# SCH_EasyEDA.net
KiCad netlist of a schematic drawn in EasyEDA
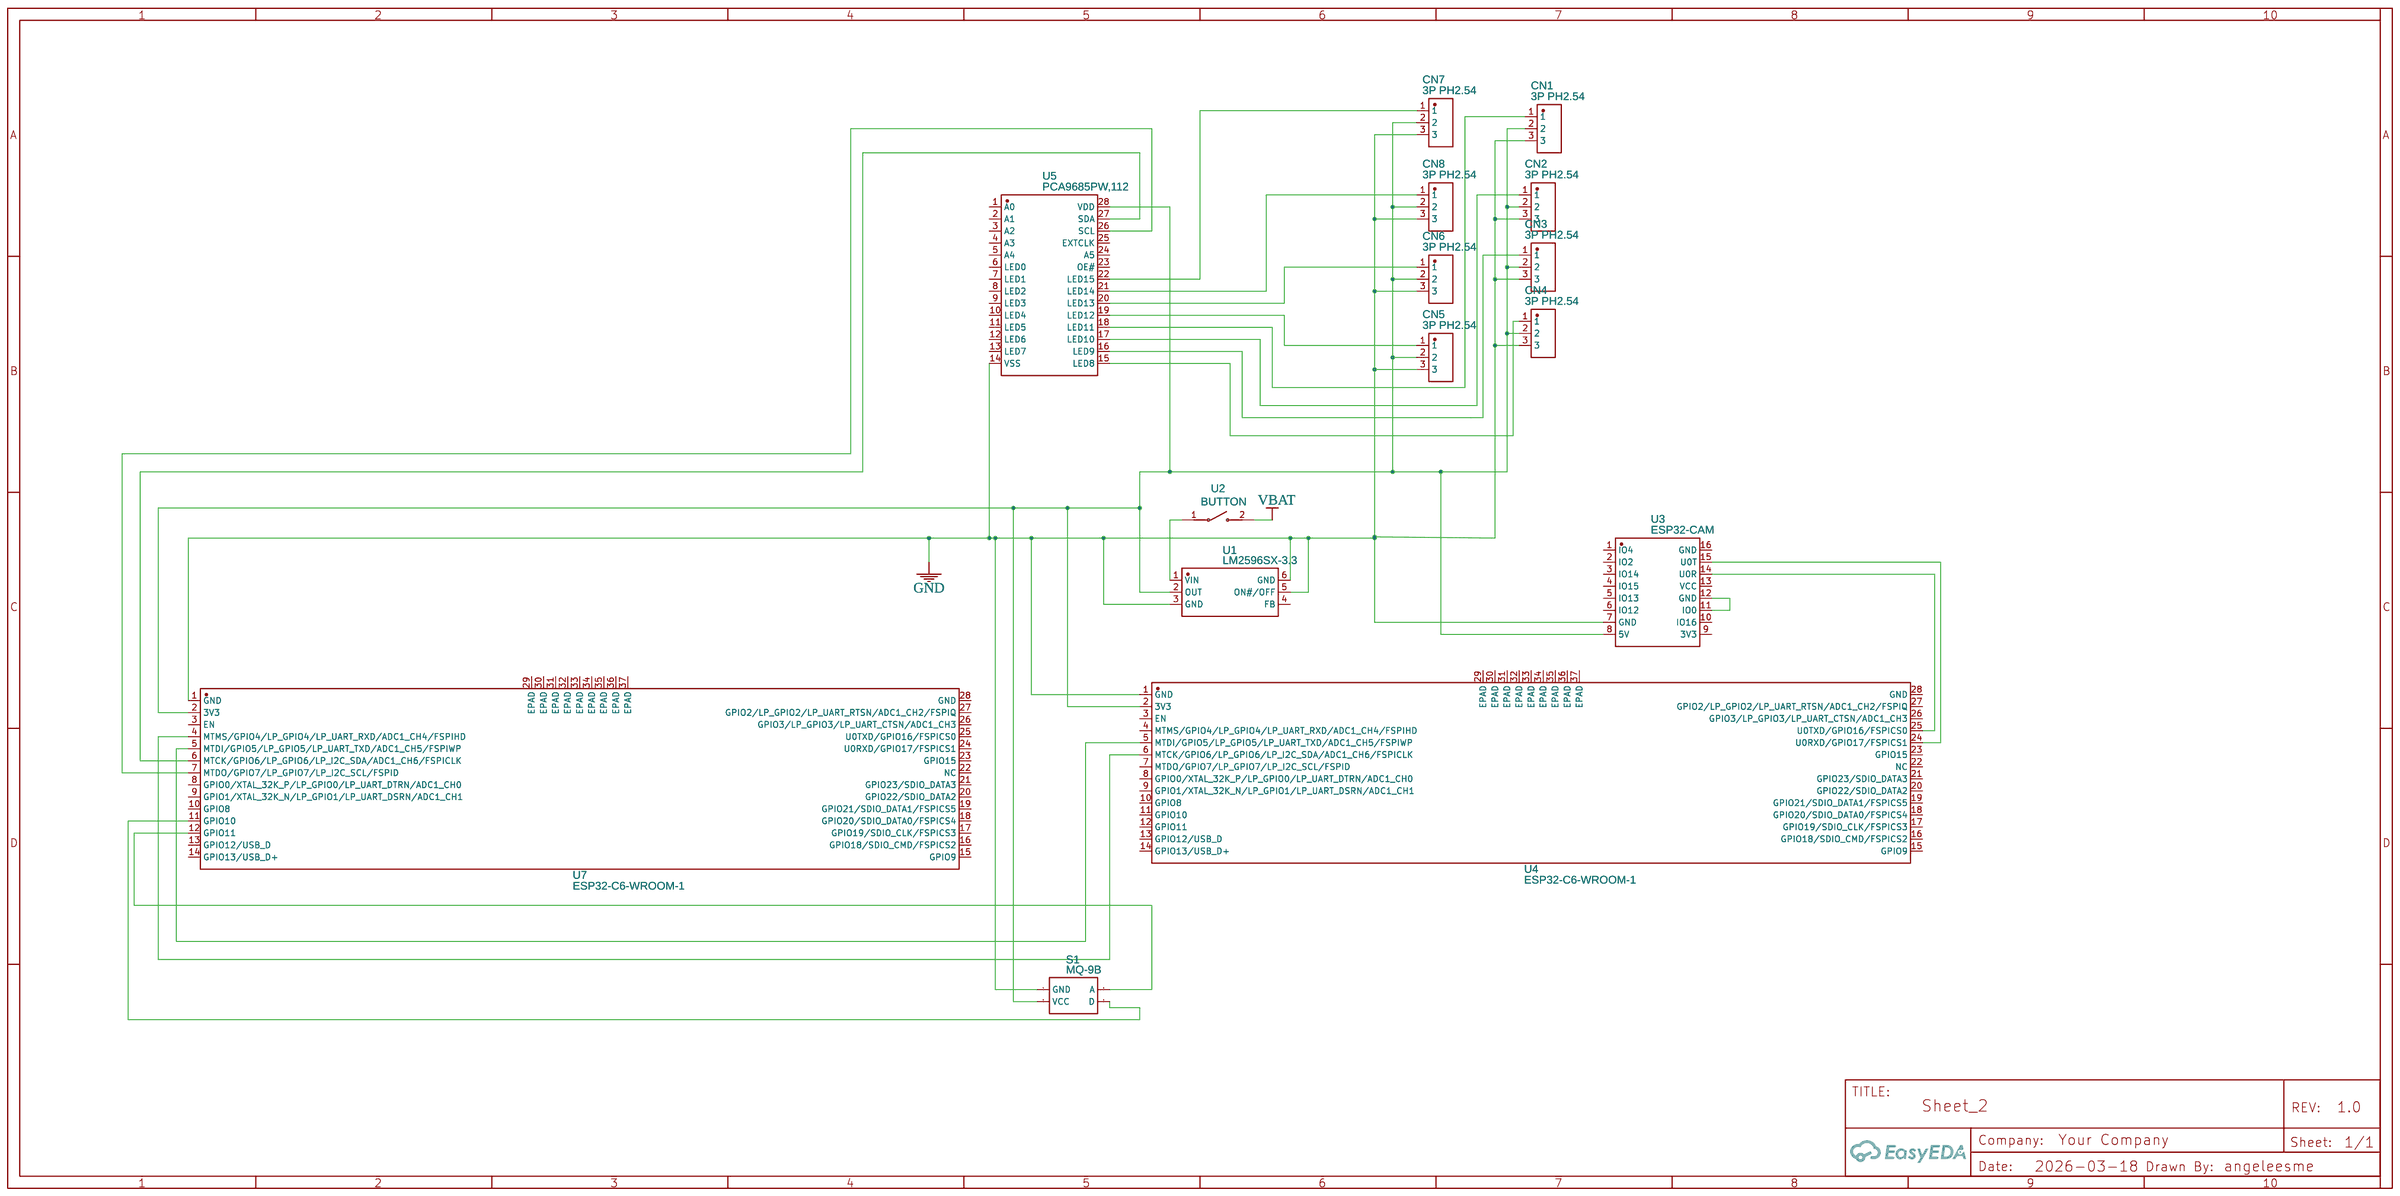
[diagram p0: schematic sheet]

(export (version "E")
  (design (tool "Eeschema 10.0.6"))
  (components
    (comp (ref "CN1") (value "3P PH2.54") (libsource (lib "") (part "3P PH2.54")))
    (comp (ref "CN2") (value "3P PH2.54") (libsource (lib "") (part "3P PH2.54")))
    (comp (ref "CN3") (value "3P PH2.54") (libsource (lib "") (part "3P PH2.54")))
    (comp (ref "CN4") (value "3P PH2.54") (libsource (lib "") (part "3P PH2.54")))
    (comp (ref "CN5") (value "3P PH2.54") (libsource (lib "") (part "3P PH2.54")))
    (comp (ref "CN6") (value "3P PH2.54") (libsource (lib "") (part "3P PH2.54")))
    (comp (ref "CN7") (value "3P PH2.54") (libsource (lib "") (part "3P PH2.54")))
    (comp (ref "CN8") (value "3P PH2.54") (libsource (lib "") (part "3P PH2.54")))
    (comp (ref "S1") (value "MQ-9B") (libsource (lib "") (part "HDR-F-2.54_2x2")))
    (comp (ref "U1")
      (value "LM2596SX-3.3")
      (fields (field (name "Manufacturer") "Slkor(萨科微)"))
      (libsource (lib "") (part "LM2596SX-3.3"))
    )
    (comp (ref "U2") (value "BUTTON") (libsource (lib "") (part "BUTTON")))
    (comp (ref "U3")
      (value "ESP32-CAM")
      (fields (field (name "Manufacturer") "Ai-Thinker(安信可)"))
      (libsource (lib "") (part "ESP32-CAM"))
    )
    (comp (ref "U4") (value "ESP32-C6-WROOM-1") (libsource (lib "") (part "ESP32-C6-WROOM-1")))
    (comp (ref "U5")
      (value "PCA9685PW,112")
      (fields (field (name "Manufacturer") "NXP(恩智浦)"))
      (libsource (lib "") (part "PCA9685PW,112"))
    )
    (comp (ref "U7") (value "ESP32-C6-WROOM-1") (libsource (lib "") (part "ESP32-C6-WROOM-1")))
  )
  (nets
    (net (code "1") (name "GND") (class "Default")
      (node (ref "CN1") (pin "3") (pinfunction "3_3") (pintype "unspecified"))
      (node (ref "CN2") (pin "3") (pinfunction "3_3") (pintype "unspecified"))
      (node (ref "CN3") (pin "3") (pinfunction "3_3") (pintype "unspecified"))
      (node (ref "CN4") (pin "3") (pinfunction "3_3") (pintype "unspecified"))
      (node (ref "CN5") (pin "3") (pinfunction "3_3") (pintype "unspecified"))
      (node (ref "CN6") (pin "3") (pinfunction "3_3") (pintype "unspecified"))
      (node (ref "CN7") (pin "3") (pinfunction "3_3") (pintype "unspecified"))
      (node (ref "CN8") (pin "3") (pinfunction "3_3") (pintype "unspecified"))
      (node (ref "S1") (pin "1") (pinfunction "GND_1") (pintype "unspecified"))
      (node (ref "U1") (pin "3") (pinfunction "GND_3") (pintype "unspecified"))
      (node (ref "U1") (pin "5") (pinfunction "ON#/OFF_5") (pintype "unspecified"))
      (node (ref "U1") (pin "6") (pinfunction "GND_6") (pintype "unspecified"))
      (node (ref "U3") (pin "7") (pinfunction "GND_7") (pintype "unspecified"))
      (node (ref "U4") (pin "1") (pinfunction "GND_1") (pintype "unspecified"))
      (node (ref "U5") (pin "14") (pinfunction "VSS_14") (pintype "unspecified"))
      (node (ref "U7") (pin "1") (pinfunction "GND_1") (pintype "unspecified"))
    )
    (net (code "2") (name "Net-(S1-A)") (class "Default")
      (node (ref "S1") (pin "2") (pinfunction "A_2") (pintype "unspecified"))
      (node (ref "U7") (pin "12") (pinfunction "GPIO11_12") (pintype "unspecified"))
    )
    (net (code "3") (name "Net-(S1-D)") (class "Default")
      (node (ref "S1") (pin "4") (pinfunction "D_4") (pintype "unspecified"))
      (node (ref "U7") (pin "11") (pinfunction "GPIO10_11") (pintype "unspecified"))
    )
    (net (code "4") (name "Net-(S1-VCC)") (class "Default")
      (node (ref "CN1") (pin "2") (pinfunction "2_2") (pintype "unspecified"))
      (node (ref "CN2") (pin "2") (pinfunction "2_2") (pintype "unspecified"))
      (node (ref "CN3") (pin "2") (pinfunction "2_2") (pintype "unspecified"))
      (node (ref "CN4") (pin "2") (pinfunction "2_2") (pintype "unspecified"))
      (node (ref "CN5") (pin "2") (pinfunction "2_2") (pintype "unspecified"))
      (node (ref "CN6") (pin "2") (pinfunction "2_2") (pintype "unspecified"))
      (node (ref "CN7") (pin "2") (pinfunction "2_2") (pintype "unspecified"))
      (node (ref "CN8") (pin "2") (pinfunction "2_2") (pintype "unspecified"))
      (node (ref "S1") (pin "3") (pinfunction "VCC_3") (pintype "unspecified"))
      (node (ref "U1") (pin "2") (pinfunction "OUT_2") (pintype "unspecified"))
      (node (ref "U3") (pin "8") (pinfunction "5V_8") (pintype "unspecified"))
      (node (ref "U4") (pin "2") (pinfunction "3V3_2") (pintype "unspecified"))
      (node (ref "U5") (pin "28") (pinfunction "VDD_28") (pintype "unspecified"))
      (node (ref "U7") (pin "2") (pinfunction "3V3_2") (pintype "unspecified"))
    )
    (net (code "5") (name "Net-(U1-VIN)") (class "Default")
      (node (ref "U1") (pin "1") (pinfunction "VIN_1") (pintype "unspecified"))
      (node (ref "U2") (pin "1") (pinfunction "1_1") (pintype "unspecified"))
    )
    (net (code "6") (name "Net-(U3-IO0)") (class "Default")
      (node (ref "U3") (pin "11") (pinfunction "IO0_11") (pintype "unspecified"))
      (node (ref "U3") (pin "12") (pinfunction "GND_12") (pintype "unspecified"))
    )
    (net (code "7") (name "Net-(U3-U0R)") (class "Default")
      (node (ref "U3") (pin "14") (pinfunction "U0R_14") (pintype "unspecified"))
      (node (ref "U4") (pin "25") (pinfunction "U0TXD/GPIO16/FSPICS0_25") (pintype "unspecified"))
    )
    (net (code "8") (name "Net-(U3-U0T)") (class "Default")
      (node (ref "U3") (pin "15") (pinfunction "U0T_15") (pintype "unspecified"))
      (node (ref "U4") (pin "24") (pinfunction "U0RXD/GPIO17/FSPICS1_24") (pintype "unspecified"))
    )
    (net (code "9") (name "Net-(U4-MTCK{slash}GPIO6{slash}LP_GPIO6{slash}LP_I2C_SDA{slash}ADC1_CH6{slash}FSPICLK)") (class "Default")
      (node (ref "U4") (pin "6") (pinfunction "MTCK/GPIO6/LP_GPIO6/LP_I2C_SDA/ADC1_CH6/FSPICLK_6") (pintype "unspecified"))
      (node (ref "U7") (pin "4") (pinfunction "MTMS/GPIO4/LP_GPIO4/LP_UART_RXD/ADC1_CH4/FSPIHD_4") (pintype "unspecified"))
    )
    (net (code "10") (name "Net-(U4-MTDI{slash}GPIO5{slash}LP_GPIO5{slash}LP_UART_TXD{slash}ADC1_CH5{slash}FSPIWP)") (class "Default")
      (node (ref "U4") (pin "5") (pinfunction "MTDI/GPIO5/LP_GPIO5/LP_UART_TXD/ADC1_CH5/FSPIWP_5") (pintype "unspecified"))
      (node (ref "U7") (pin "5") (pinfunction "MTDI/GPIO5/LP_GPIO5/LP_UART_TXD/ADC1_CH5/FSPIWP_5") (pintype "unspecified"))
    )
    (net (code "11") (name "Net-(U5-LED8)") (class "Default")
      (node (ref "CN4") (pin "1") (pinfunction "1_1") (pintype "unspecified"))
      (node (ref "U5") (pin "15") (pinfunction "LED8_15") (pintype "unspecified"))
    )
    (net (code "12") (name "Net-(U5-LED9)") (class "Default")
      (node (ref "CN3") (pin "1") (pinfunction "1_1") (pintype "unspecified"))
      (node (ref "U5") (pin "16") (pinfunction "LED9_16") (pintype "unspecified"))
    )
    (net (code "13") (name "Net-(U5-LED10)") (class "Default")
      (node (ref "CN2") (pin "1") (pinfunction "1_1") (pintype "unspecified"))
      (node (ref "U5") (pin "17") (pinfunction "LED10_17") (pintype "unspecified"))
    )
    (net (code "14") (name "Net-(U5-LED11)") (class "Default")
      (node (ref "CN1") (pin "1") (pinfunction "1_1") (pintype "unspecified"))
      (node (ref "U5") (pin "18") (pinfunction "LED11_18") (pintype "unspecified"))
    )
    (net (code "15") (name "Net-(U5-LED12)") (class "Default")
      (node (ref "CN5") (pin "1") (pinfunction "1_1") (pintype "unspecified"))
      (node (ref "U5") (pin "19") (pinfunction "LED12_19") (pintype "unspecified"))
    )
    (net (code "16") (name "Net-(U5-LED13)") (class "Default")
      (node (ref "CN6") (pin "1") (pinfunction "1_1") (pintype "unspecified"))
      (node (ref "U5") (pin "20") (pinfunction "LED13_20") (pintype "unspecified"))
    )
    (net (code "17") (name "Net-(U5-LED14)") (class "Default")
      (node (ref "CN8") (pin "1") (pinfunction "1_1") (pintype "unspecified"))
      (node (ref "U5") (pin "21") (pinfunction "LED14_21") (pintype "unspecified"))
    )
    (net (code "18") (name "Net-(U5-LED15)") (class "Default")
      (node (ref "CN7") (pin "1") (pinfunction "1_1") (pintype "unspecified"))
      (node (ref "U5") (pin "22") (pinfunction "LED15_22") (pintype "unspecified"))
    )
    (net (code "19") (name "Net-(U5-SCL)") (class "Default")
      (node (ref "U5") (pin "26") (pinfunction "SCL_26") (pintype "unspecified"))
      (node (ref "U7") (pin "7") (pinfunction "MTDO/GPIO7/LP_GPIO7/LP_I2C_SCL/FSPID_7") (pintype "unspecified"))
    )
    (net (code "20") (name "Net-(U5-SDA)") (class "Default")
      (node (ref "U5") (pin "27") (pinfunction "SDA_27") (pintype "unspecified"))
      (node (ref "U7") (pin "6") (pinfunction "MTCK/GPIO6/LP_GPIO6/LP_I2C_SDA/ADC1_CH6/FSPICLK_6") (pintype "unspecified"))
    )
    (net (code "21") (name "VBAT") (class "Default")
      (node (ref "U2") (pin "2") (pinfunction "2_2") (pintype "unspecified"))
    )
    (net (code "22") (name "unconnected-(U1-FB-Pad4)") (class "Default")
      (node (ref "U1") (pin "4") (pinfunction "FB_4") (pintype "unspecified"))
    )
    (net (code "23") (name "unconnected-(U3-3V3-Pad9)") (class "Default")
      (node (ref "U3") (pin "9") (pinfunction "3V3_9") (pintype "unspecified"))
    )
    (net (code "24") (name "unconnected-(U3-GND-Pad16)") (class "Default")
      (node (ref "U3") (pin "16") (pinfunction "GND_16") (pintype "unspecified"))
    )
    (net (code "25") (name "unconnected-(U3-IO2-Pad2)") (class "Default")
      (node (ref "U3") (pin "2") (pinfunction "IO2_2") (pintype "unspecified"))
    )
    (net (code "26") (name "unconnected-(U3-IO4-Pad1)") (class "Default")
      (node (ref "U3") (pin "1") (pinfunction "IO4_1") (pintype "unspecified"))
    )
    (net (code "27") (name "unconnected-(U3-IO12-Pad6)") (class "Default")
      (node (ref "U3") (pin "6") (pinfunction "IO12_6") (pintype "unspecified"))
    )
    (net (code "28") (name "unconnected-(U3-IO13-Pad5)") (class "Default")
      (node (ref "U3") (pin "5") (pinfunction "IO13_5") (pintype "unspecified"))
    )
    (net (code "29") (name "unconnected-(U3-IO14-Pad3)") (class "Default")
      (node (ref "U3") (pin "3") (pinfunction "IO14_3") (pintype "unspecified"))
    )
    (net (code "30") (name "unconnected-(U3-IO15-Pad4)") (class "Default")
      (node (ref "U3") (pin "4") (pinfunction "IO15_4") (pintype "unspecified"))
    )
    (net (code "31") (name "unconnected-(U3-IO16-Pad10)") (class "Default")
      (node (ref "U3") (pin "10") (pinfunction "IO16_10") (pintype "unspecified"))
    )
    (net (code "32") (name "unconnected-(U3-VCC-Pad13)") (class "Default")
      (node (ref "U3") (pin "13") (pinfunction "VCC_13") (pintype "unspecified"))
    )
    (net (code "33") (name "unconnected-(U4-EN-Pad3)") (class "Default")
      (node (ref "U4") (pin "3") (pinfunction "EN_3") (pintype "unspecified"))
    )
    (net (code "34") (name "unconnected-(U4-EPAD-Pad29)") (class "Default")
      (node (ref "U4") (pin "29") (pinfunction "EPAD_29") (pintype "unspecified"))
    )
    (net (code "35") (name "unconnected-(U4-EPAD-Pad30)") (class "Default")
      (node (ref "U4") (pin "30") (pinfunction "EPAD_30") (pintype "unspecified"))
    )
    (net (code "36") (name "unconnected-(U4-EPAD-Pad31)") (class "Default")
      (node (ref "U4") (pin "31") (pinfunction "EPAD_31") (pintype "unspecified"))
    )
    (net (code "37") (name "unconnected-(U4-EPAD-Pad32)") (class "Default")
      (node (ref "U4") (pin "32") (pinfunction "EPAD_32") (pintype "unspecified"))
    )
    (net (code "38") (name "unconnected-(U4-EPAD-Pad33)") (class "Default")
      (node (ref "U4") (pin "33") (pinfunction "EPAD_33") (pintype "unspecified"))
    )
    (net (code "39") (name "unconnected-(U4-EPAD-Pad34)") (class "Default")
      (node (ref "U4") (pin "34") (pinfunction "EPAD_34") (pintype "unspecified"))
    )
    (net (code "40") (name "unconnected-(U4-EPAD-Pad35)") (class "Default")
      (node (ref "U4") (pin "35") (pinfunction "EPAD_35") (pintype "unspecified"))
    )
    (net (code "41") (name "unconnected-(U4-EPAD-Pad36)") (class "Default")
      (node (ref "U4") (pin "36") (pinfunction "EPAD_36") (pintype "unspecified"))
    )
    (net (code "42") (name "unconnected-(U4-EPAD-Pad37)") (class "Default")
      (node (ref "U4") (pin "37") (pinfunction "EPAD_37") (pintype "unspecified"))
    )
    (net (code "43") (name "unconnected-(U4-GND-Pad28)") (class "Default")
      (node (ref "U4") (pin "28") (pinfunction "GND_28") (pintype "unspecified"))
    )
    (net (code "44") (name "unconnected-(U4-GPIO0{slash}XTAL_32K_P{slash}LP_GPIO0{slash}LP_UART_DTRN{slash}ADC1_CH0-Pad8)") (class "Default")
      (node (ref "U4") (pin "8") (pinfunction "GPIO0/XTAL_32K_P/LP_GPIO0/LP_UART_DTRN/ADC1_CH0_8") (pintype "unspecified"))
    )
    (net (code "45") (name "unconnected-(U4-GPIO1{slash}XTAL_32K_N{slash}LP_GPIO1{slash}LP_UART_DSRN{slash}ADC1_CH1-Pad9)") (class "Default")
      (node (ref "U4") (pin "9") (pinfunction "GPIO1/XTAL_32K_N/LP_GPIO1/LP_UART_DSRN/ADC1_CH1_9") (pintype "unspecified"))
    )
    (net (code "46") (name "unconnected-(U4-GPIO2{slash}LP_GPIO2{slash}LP_UART_RTSN{slash}ADC1_CH2{slash}FSPIQ-Pad27)") (class "Default")
      (node (ref "U4") (pin "27") (pinfunction "GPIO2/LP_GPIO2/LP_UART_RTSN/ADC1_CH2/FSPIQ_27") (pintype "unspecified"))
    )
    (net (code "47") (name "unconnected-(U4-GPIO3{slash}LP_GPIO3{slash}LP_UART_CTSN{slash}ADC1_CH3-Pad26)") (class "Default")
      (node (ref "U4") (pin "26") (pinfunction "GPIO3/LP_GPIO3/LP_UART_CTSN/ADC1_CH3_26") (pintype "unspecified"))
    )
    (net (code "48") (name "unconnected-(U4-GPIO8-Pad10)") (class "Default")
      (node (ref "U4") (pin "10") (pinfunction "GPIO8_10") (pintype "unspecified"))
    )
    (net (code "49") (name "unconnected-(U4-GPIO9-Pad15)") (class "Default")
      (node (ref "U4") (pin "15") (pinfunction "GPIO9_15") (pintype "unspecified"))
    )
    (net (code "50") (name "unconnected-(U4-GPIO10-Pad11)") (class "Default")
      (node (ref "U4") (pin "11") (pinfunction "GPIO10_11") (pintype "unspecified"))
    )
    (net (code "51") (name "unconnected-(U4-GPIO11-Pad12)") (class "Default")
      (node (ref "U4") (pin "12") (pinfunction "GPIO11_12") (pintype "unspecified"))
    )
    (net (code "52") (name "unconnected-(U4-GPIO12{slash}USB_D-Pad13)") (class "Default")
      (node (ref "U4") (pin "13") (pinfunction "GPIO12/USB_D_13") (pintype "unspecified"))
    )
    (net (code "53") (name "unconnected-(U4-GPIO13{slash}USB_D+-Pad14)") (class "Default")
      (node (ref "U4") (pin "14") (pinfunction "GPIO13/USB_D+_14") (pintype "unspecified"))
    )
    (net (code "54") (name "unconnected-(U4-GPIO15-Pad23)") (class "Default")
      (node (ref "U4") (pin "23") (pinfunction "GPIO15_23") (pintype "unspecified"))
    )
    (net (code "55") (name "unconnected-(U4-GPIO18{slash}SDIO_CMD{slash}FSPICS2-Pad16)") (class "Default")
      (node (ref "U4") (pin "16") (pinfunction "GPIO18/SDIO_CMD/FSPICS2_16") (pintype "unspecified"))
    )
    (net (code "56") (name "unconnected-(U4-GPIO19{slash}SDIO_CLK{slash}FSPICS3-Pad17)") (class "Default")
      (node (ref "U4") (pin "17") (pinfunction "GPIO19/SDIO_CLK/FSPICS3_17") (pintype "unspecified"))
    )
    (net (code "57") (name "unconnected-(U4-GPIO20{slash}SDIO_DATA0{slash}FSPICS4-Pad18)") (class "Default")
      (node (ref "U4") (pin "18") (pinfunction "GPIO20/SDIO_DATA0/FSPICS4_18") (pintype "unspecified"))
    )
    (net (code "58") (name "unconnected-(U4-GPIO21{slash}SDIO_DATA1{slash}FSPICS5-Pad19)") (class "Default")
      (node (ref "U4") (pin "19") (pinfunction "GPIO21/SDIO_DATA1/FSPICS5_19") (pintype "unspecified"))
    )
    (net (code "59") (name "unconnected-(U4-GPIO22{slash}SDIO_DATA2-Pad20)") (class "Default")
      (node (ref "U4") (pin "20") (pinfunction "GPIO22/SDIO_DATA2_20") (pintype "unspecified"))
    )
    (net (code "60") (name "unconnected-(U4-GPIO23{slash}SDIO_DATA3-Pad21)") (class "Default")
      (node (ref "U4") (pin "21") (pinfunction "GPIO23/SDIO_DATA3_21") (pintype "unspecified"))
    )
    (net (code "61") (name "unconnected-(U4-MTDO{slash}GPIO7{slash}LP_GPIO7{slash}LP_I2C_SCL{slash}FSPID-Pad7)") (class "Default")
      (node (ref "U4") (pin "7") (pinfunction "MTDO/GPIO7/LP_GPIO7/LP_I2C_SCL/FSPID_7") (pintype "unspecified"))
    )
    (net (code "62") (name "unconnected-(U4-MTMS{slash}GPIO4{slash}LP_GPIO4{slash}LP_UART_RXD{slash}ADC1_CH4{slash}FSPIHD-Pad4)") (class "Default")
      (node (ref "U4") (pin "4") (pinfunction "MTMS/GPIO4/LP_GPIO4/LP_UART_RXD/ADC1_CH4/FSPIHD_4") (pintype "unspecified"))
    )
    (net (code "63") (name "unconnected-(U4-NC-Pad22)") (class "Default")
      (node (ref "U4") (pin "22") (pinfunction "NC_22") (pintype "unspecified"))
    )
    (net (code "64") (name "unconnected-(U5-A0-Pad1)") (class "Default")
      (node (ref "U5") (pin "1") (pinfunction "A0_1") (pintype "unspecified"))
    )
    (net (code "65") (name "unconnected-(U5-A1-Pad2)") (class "Default")
      (node (ref "U5") (pin "2") (pinfunction "A1_2") (pintype "unspecified"))
    )
    (net (code "66") (name "unconnected-(U5-A2-Pad3)") (class "Default")
      (node (ref "U5") (pin "3") (pinfunction "A2_3") (pintype "unspecified"))
    )
    (net (code "67") (name "unconnected-(U5-A3-Pad4)") (class "Default")
      (node (ref "U5") (pin "4") (pinfunction "A3_4") (pintype "unspecified"))
    )
    (net (code "68") (name "unconnected-(U5-A4-Pad5)") (class "Default")
      (node (ref "U5") (pin "5") (pinfunction "A4_5") (pintype "unspecified"))
    )
    (net (code "69") (name "unconnected-(U5-A5-Pad24)") (class "Default")
      (node (ref "U5") (pin "24") (pinfunction "A5_24") (pintype "unspecified"))
    )
    (net (code "70") (name "unconnected-(U5-EXTCLK-Pad25)") (class "Default")
      (node (ref "U5") (pin "25") (pinfunction "EXTCLK_25") (pintype "unspecified"))
    )
    (net (code "71") (name "unconnected-(U5-LED0-Pad6)") (class "Default")
      (node (ref "U5") (pin "6") (pinfunction "LED0_6") (pintype "unspecified"))
    )
    (net (code "72") (name "unconnected-(U5-LED1-Pad7)") (class "Default")
      (node (ref "U5") (pin "7") (pinfunction "LED1_7") (pintype "unspecified"))
    )
    (net (code "73") (name "unconnected-(U5-LED2-Pad8)") (class "Default")
      (node (ref "U5") (pin "8") (pinfunction "LED2_8") (pintype "unspecified"))
    )
    (net (code "74") (name "unconnected-(U5-LED3-Pad9)") (class "Default")
      (node (ref "U5") (pin "9") (pinfunction "LED3_9") (pintype "unspecified"))
    )
    (net (code "75") (name "unconnected-(U5-LED4-Pad10)") (class "Default")
      (node (ref "U5") (pin "10") (pinfunction "LED4_10") (pintype "unspecified"))
    )
    (net (code "76") (name "unconnected-(U5-LED5-Pad11)") (class "Default")
      (node (ref "U5") (pin "11") (pinfunction "LED5_11") (pintype "unspecified"))
    )
    (net (code "77") (name "unconnected-(U5-LED6-Pad12)") (class "Default")
      (node (ref "U5") (pin "12") (pinfunction "LED6_12") (pintype "unspecified"))
    )
    (net (code "78") (name "unconnected-(U5-LED7-Pad13)") (class "Default")
      (node (ref "U5") (pin "13") (pinfunction "LED7_13") (pintype "unspecified"))
    )
    (net (code "79") (name "unconnected-(U5-OE#-Pad23)") (class "Default")
      (node (ref "U5") (pin "23") (pinfunction "OE#_23") (pintype "unspecified"))
    )
    (net (code "80") (name "unconnected-(U7-EN-Pad3)") (class "Default")
      (node (ref "U7") (pin "3") (pinfunction "EN_3") (pintype "unspecified"))
    )
    (net (code "81") (name "unconnected-(U7-EPAD-Pad29)") (class "Default")
      (node (ref "U7") (pin "29") (pinfunction "EPAD_29") (pintype "unspecified"))
    )
    (net (code "82") (name "unconnected-(U7-EPAD-Pad30)") (class "Default")
      (node (ref "U7") (pin "30") (pinfunction "EPAD_30") (pintype "unspecified"))
    )
    (net (code "83") (name "unconnected-(U7-EPAD-Pad31)") (class "Default")
      (node (ref "U7") (pin "31") (pinfunction "EPAD_31") (pintype "unspecified"))
    )
    (net (code "84") (name "unconnected-(U7-EPAD-Pad32)") (class "Default")
      (node (ref "U7") (pin "32") (pinfunction "EPAD_32") (pintype "unspecified"))
    )
    (net (code "85") (name "unconnected-(U7-EPAD-Pad33)") (class "Default")
      (node (ref "U7") (pin "33") (pinfunction "EPAD_33") (pintype "unspecified"))
    )
    (net (code "86") (name "unconnected-(U7-EPAD-Pad34)") (class "Default")
      (node (ref "U7") (pin "34") (pinfunction "EPAD_34") (pintype "unspecified"))
    )
    (net (code "87") (name "unconnected-(U7-EPAD-Pad35)") (class "Default")
      (node (ref "U7") (pin "35") (pinfunction "EPAD_35") (pintype "unspecified"))
    )
    (net (code "88") (name "unconnected-(U7-EPAD-Pad36)") (class "Default")
      (node (ref "U7") (pin "36") (pinfunction "EPAD_36") (pintype "unspecified"))
    )
    (net (code "89") (name "unconnected-(U7-EPAD-Pad37)") (class "Default")
      (node (ref "U7") (pin "37") (pinfunction "EPAD_37") (pintype "unspecified"))
    )
    (net (code "90") (name "unconnected-(U7-GND-Pad28)") (class "Default")
      (node (ref "U7") (pin "28") (pinfunction "GND_28") (pintype "unspecified"))
    )
    (net (code "91") (name "unconnected-(U7-GPIO0{slash}XTAL_32K_P{slash}LP_GPIO0{slash}LP_UART_DTRN{slash}ADC1_CH0-Pad8)") (class "Default")
      (node (ref "U7") (pin "8") (pinfunction "GPIO0/XTAL_32K_P/LP_GPIO0/LP_UART_DTRN/ADC1_CH0_8") (pintype "unspecified"))
    )
    (net (code "92") (name "unconnected-(U7-GPIO1{slash}XTAL_32K_N{slash}LP_GPIO1{slash}LP_UART_DSRN{slash}ADC1_CH1-Pad9)") (class "Default")
      (node (ref "U7") (pin "9") (pinfunction "GPIO1/XTAL_32K_N/LP_GPIO1/LP_UART_DSRN/ADC1_CH1_9") (pintype "unspecified"))
    )
    (net (code "93") (name "unconnected-(U7-GPIO2{slash}LP_GPIO2{slash}LP_UART_RTSN{slash}ADC1_CH2{slash}FSPIQ-Pad27)") (class "Default")
      (node (ref "U7") (pin "27") (pinfunction "GPIO2/LP_GPIO2/LP_UART_RTSN/ADC1_CH2/FSPIQ_27") (pintype "unspecified"))
    )
    (net (code "94") (name "unconnected-(U7-GPIO3{slash}LP_GPIO3{slash}LP_UART_CTSN{slash}ADC1_CH3-Pad26)") (class "Default")
      (node (ref "U7") (pin "26") (pinfunction "GPIO3/LP_GPIO3/LP_UART_CTSN/ADC1_CH3_26") (pintype "unspecified"))
    )
    (net (code "95") (name "unconnected-(U7-GPIO8-Pad10)") (class "Default")
      (node (ref "U7") (pin "10") (pinfunction "GPIO8_10") (pintype "unspecified"))
    )
    (net (code "96") (name "unconnected-(U7-GPIO9-Pad15)") (class "Default")
      (node (ref "U7") (pin "15") (pinfunction "GPIO9_15") (pintype "unspecified"))
    )
    (net (code "97") (name "unconnected-(U7-GPIO12{slash}USB_D-Pad13)") (class "Default")
      (node (ref "U7") (pin "13") (pinfunction "GPIO12/USB_D_13") (pintype "unspecified"))
    )
    (net (code "98") (name "unconnected-(U7-GPIO13{slash}USB_D+-Pad14)") (class "Default")
      (node (ref "U7") (pin "14") (pinfunction "GPIO13/USB_D+_14") (pintype "unspecified"))
    )
    (net (code "99") (name "unconnected-(U7-GPIO15-Pad23)") (class "Default")
      (node (ref "U7") (pin "23") (pinfunction "GPIO15_23") (pintype "unspecified"))
    )
    (net (code "100") (name "unconnected-(U7-GPIO18{slash}SDIO_CMD{slash}FSPICS2-Pad16)") (class "Default")
      (node (ref "U7") (pin "16") (pinfunction "GPIO18/SDIO_CMD/FSPICS2_16") (pintype "unspecified"))
    )
    (net (code "101") (name "unconnected-(U7-GPIO19{slash}SDIO_CLK{slash}FSPICS3-Pad17)") (class "Default")
      (node (ref "U7") (pin "17") (pinfunction "GPIO19/SDIO_CLK/FSPICS3_17") (pintype "unspecified"))
    )
    (net (code "102") (name "unconnected-(U7-GPIO20{slash}SDIO_DATA0{slash}FSPICS4-Pad18)") (class "Default")
      (node (ref "U7") (pin "18") (pinfunction "GPIO20/SDIO_DATA0/FSPICS4_18") (pintype "unspecified"))
    )
    (net (code "103") (name "unconnected-(U7-GPIO21{slash}SDIO_DATA1{slash}FSPICS5-Pad19)") (class "Default")
      (node (ref "U7") (pin "19") (pinfunction "GPIO21/SDIO_DATA1/FSPICS5_19") (pintype "unspecified"))
    )
    (net (code "104") (name "unconnected-(U7-GPIO22{slash}SDIO_DATA2-Pad20)") (class "Default")
      (node (ref "U7") (pin "20") (pinfunction "GPIO22/SDIO_DATA2_20") (pintype "unspecified"))
    )
    (net (code "105") (name "unconnected-(U7-GPIO23{slash}SDIO_DATA3-Pad21)") (class "Default")
      (node (ref "U7") (pin "21") (pinfunction "GPIO23/SDIO_DATA3_21") (pintype "unspecified"))
    )
    (net (code "106") (name "unconnected-(U7-NC-Pad22)") (class "Default")
      (node (ref "U7") (pin "22") (pinfunction "NC_22") (pintype "unspecified"))
    )
    (net (code "107") (name "unconnected-(U7-U0RXD{slash}GPIO17{slash}FSPICS1-Pad24)") (class "Default")
      (node (ref "U7") (pin "24") (pinfunction "U0RXD/GPIO17/FSPICS1_24") (pintype "unspecified"))
    )
    (net (code "108") (name "unconnected-(U7-U0TXD{slash}GPIO16{slash}FSPICS0-Pad25)") (class "Default")
      (node (ref "U7") (pin "25") (pinfunction "U0TXD/GPIO16/FSPICS0_25") (pintype "unspecified"))
    )
  )
)
